# 08_-_CPU_TF_CARD_USB_OTG.net
KiCad netlist of a schematic drawn in Altium Designer
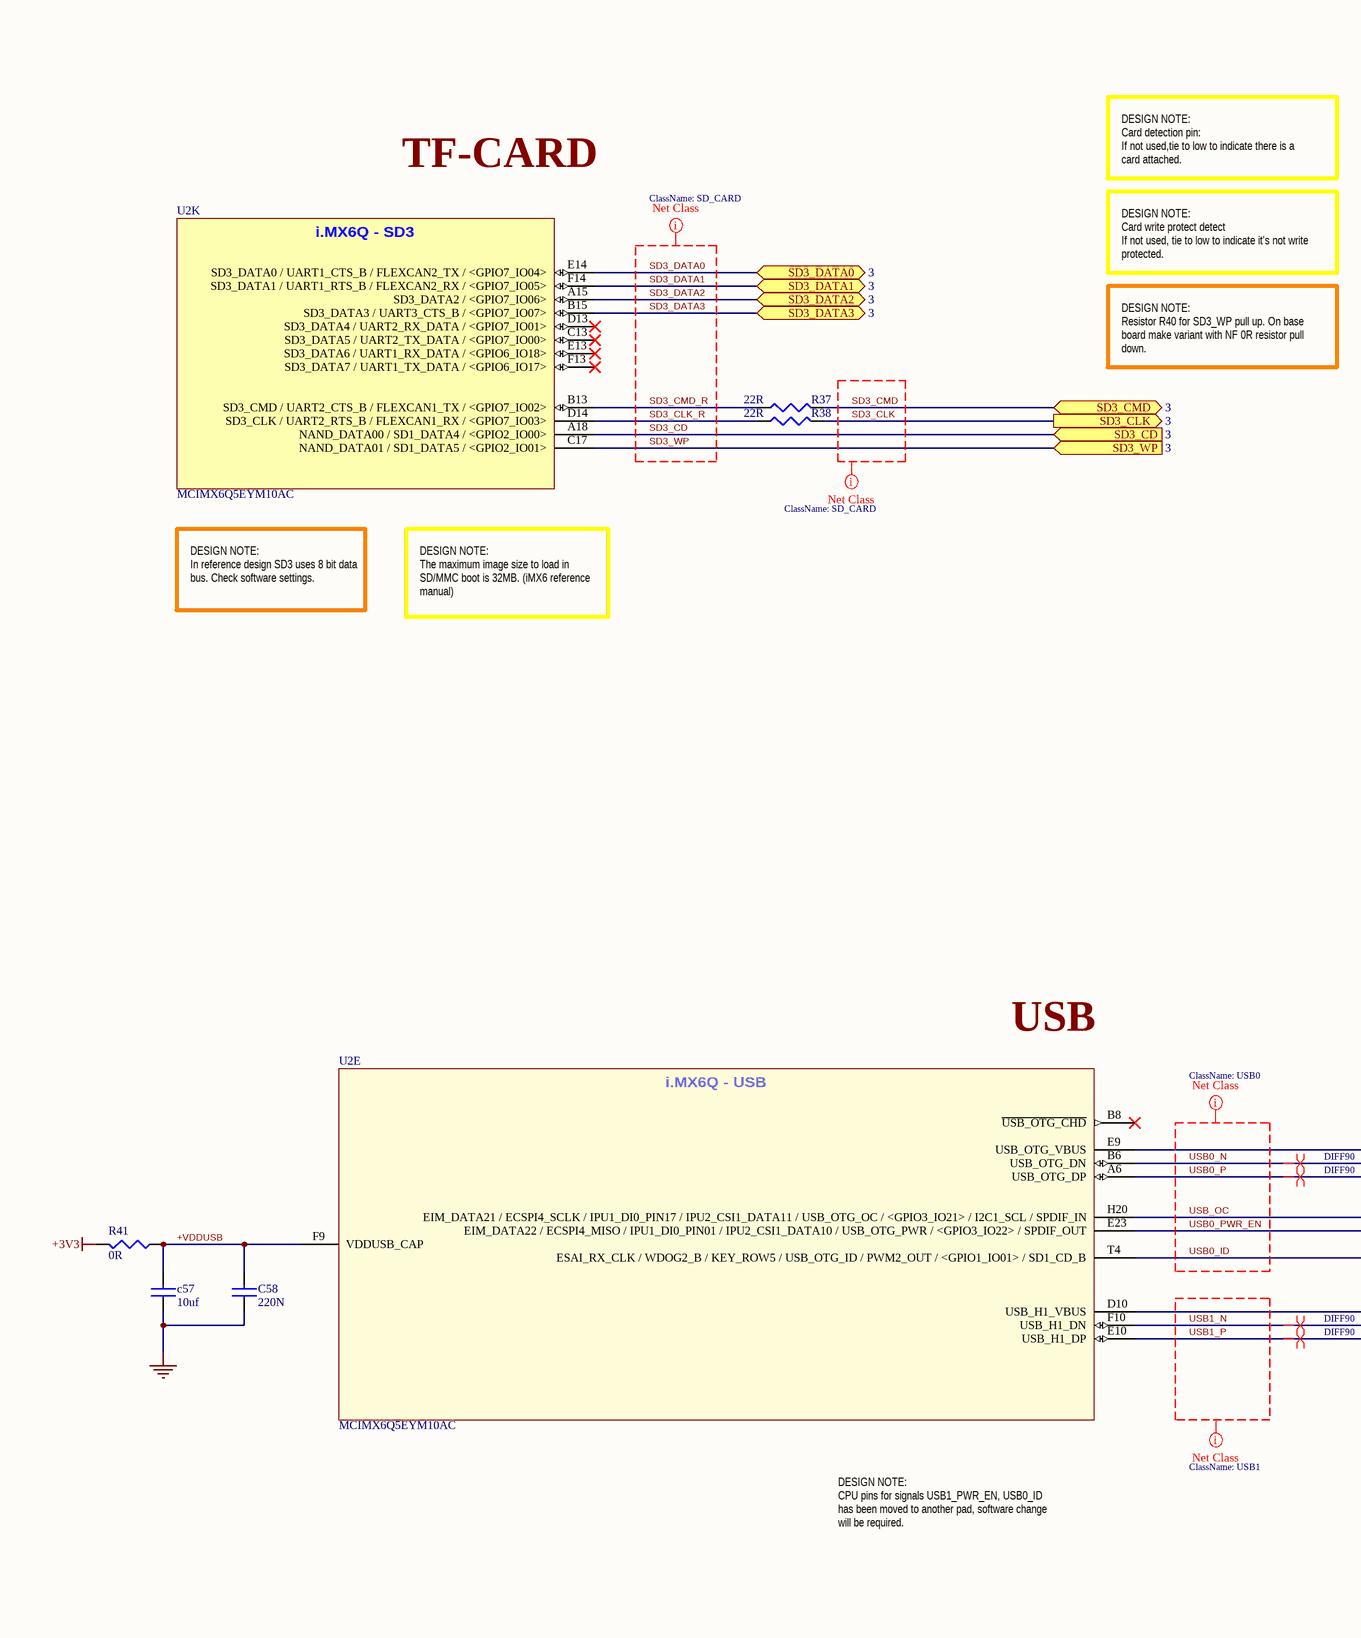
[diagram p0: [08] - CPU TF_CARD,USB OTG.SchDoc, left]
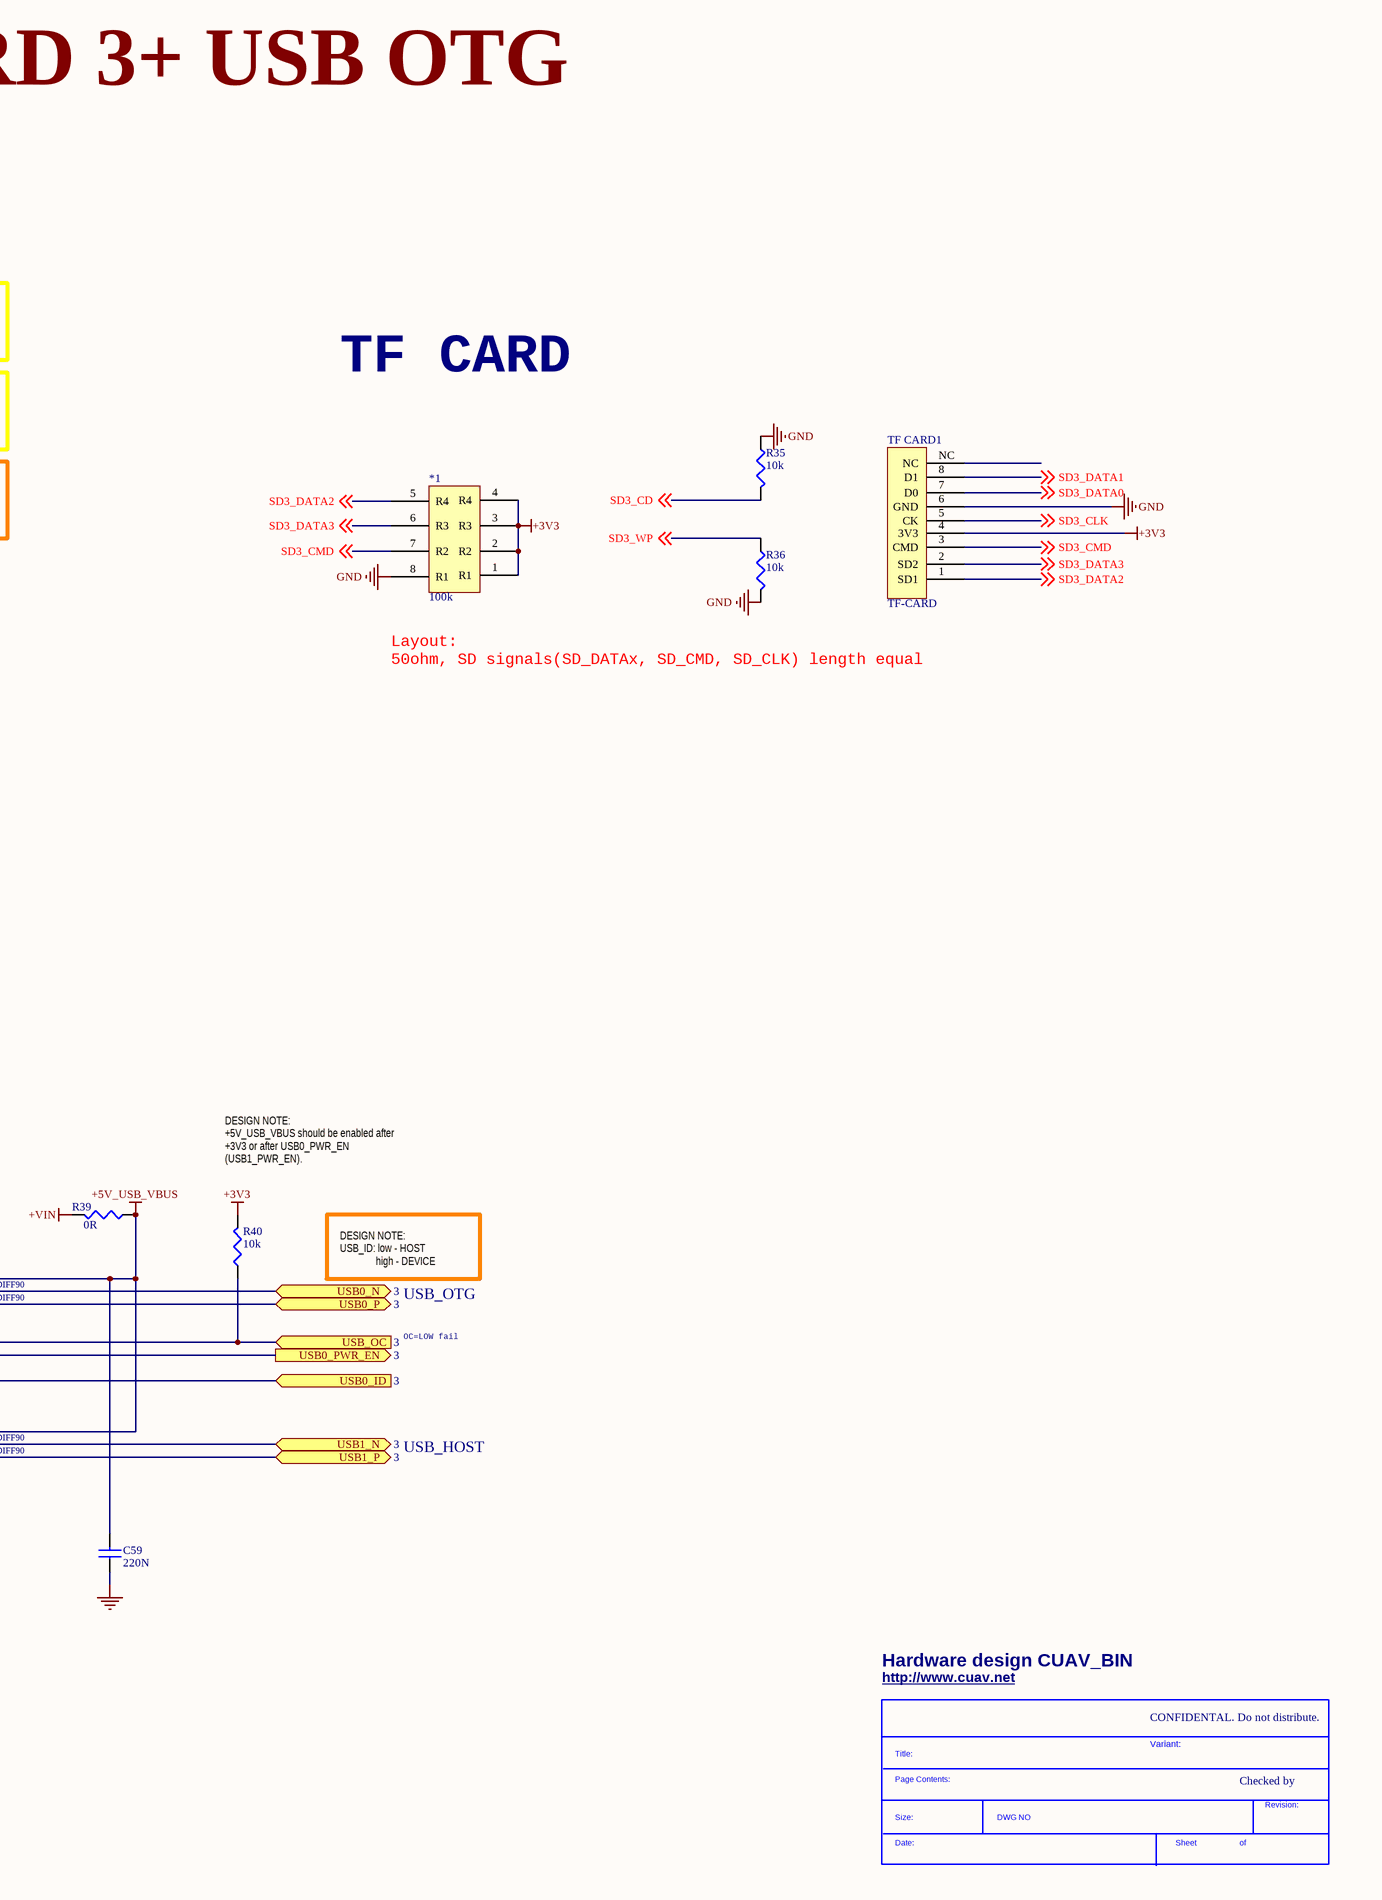
[diagram p1: [08] - CPU TF_CARD,USB OTG.SchDoc, right]

(export (version "E")
  (design (tool "Eeschema 10.0.6"))
  (components
    (comp (ref "*") (value "SDTitleBlock") (libsource (lib "*") (part "SDTitleBlock")))
    (comp (ref "*1") (value "100k") (footprint "0402_4R") (libsource (lib "hack") (part "0402_4R")))
    (comp (ref "c57")
      (value "10uf")
      (footprint "0402cap")
      (description "CAP CER .10UF 50V X5R 10% 0402")
      (fields
        (field (name "MANUFACTURER") "TDK Corporation")
        (field (name "MANUFACTURER PART NUMBER") "C1005X5R1H104K")
      )
      (libsource (lib "Integrated_Library_RF_FEB_2012") (part "C1005X5R1H104K"))
    )
    (comp (ref "C58")
      (value "220N")
      (footprint "0402cap")
      (description "CAP CER .10UF 50V X5R 10% 0402")
      (fields
        (field (name "MANUFACTURER") "TDK Corporation")
        (field (name "MANUFACTURER PART NUMBER") "C1005X5R1H104K")
      )
      (libsource (lib "Integrated_Library_RF_FEB_2012") (part "C1005X5R1H104K"))
    )
    (comp (ref "C59")
      (value "220N")
      (footprint "0402cap")
      (description "CAP CER .10UF 50V X5R 10% 0402")
      (fields
        (field (name "MANUFACTURER") "TDK Corporation")
        (field (name "MANUFACTURER PART NUMBER") "C1005X5R1H104K")
      )
      (libsource (lib "Integrated_Library_RF_FEB_2012") (part "C1005X5R1H104K"))
    )
    (comp (ref "R35")
      (value "10k")
      (footprint "R0402")
      (description "RES 10.0K OHM 1/16W 1% 0402 SMD")
      (fields
        (field (name "MANUFACTURER") "Yageo")
        (field (name "MANUFACTURER PART NUMBER") "RC0402FR-0710KL")
      )
      (libsource (lib "Integrated_Library_RF_FEB_2012") (part "RC0402FR-0710KL"))
    )
    (comp (ref "R36")
      (value "10k")
      (footprint "R0402")
      (description "RES 10.0K OHM 1/16W 1% 0402 SMD")
      (fields
        (field (name "MANUFACTURER") "Yageo")
        (field (name "MANUFACTURER PART NUMBER") "RC0402FR-0710KL")
      )
      (libsource (lib "Integrated_Library_RF_FEB_2012") (part "RC0402FR-0710KL"))
    )
    (comp (ref "R37")
      (value "22R")
      (footprint "R0402")
      (description "RES 22.0 OHM 1/16W 1% 0402 SMD")
      (fields
        (field (name "MANUFACTURER") "Yageo")
        (field (name "MANUFACTURER PART NUMBER") "RC0402FR-0722RL")
      )
      (libsource (lib "Integrated_Library_RF_FEB_2012") (part "RC0402FR-0722RL"))
    )
    (comp (ref "R38")
      (value "22R")
      (footprint "R0402")
      (description "RES 22.0 OHM 1/16W 1% 0402 SMD")
      (fields
        (field (name "MANUFACTURER") "Yageo")
        (field (name "MANUFACTURER PART NUMBER") "RC0402FR-0722RL")
      )
      (libsource (lib "Integrated_Library_RF_FEB_2012") (part "RC0402FR-0722RL"))
    )
    (comp (ref "R39")
      (value "0R")
      (footprint "R0402")
      (description "RES 39.0K OHM 1/16W 1% 0402 SMD")
      (fields
        (field (name "MANUFACTURER") "Yageo")
        (field (name "MANUFACTURER PART NUMBER") "RC0402FR-0739KL")
      )
      (libsource (lib "Integrated_Library_RF_FEB_2012") (part "RC0402FR-0739KL"))
    )
    (comp (ref "R40")
      (value "10k")
      (footprint "R0402")
      (description "RES 10.0K OHM 1/16W 1% 0402 SMD")
      (fields
        (field (name "MANUFACTURER") "Yageo")
        (field (name "MANUFACTURER PART NUMBER") "RC0402FR-0710KL")
      )
      (libsource (lib "Integrated_Library_RF_FEB_2012") (part "RC0402FR-0710KL"))
    )
    (comp (ref "R41")
      (value "0R")
      (footprint "R0402")
      (description "RES 39.0K OHM 1/16W 1% 0402 SMD")
      (fields
        (field (name "MANUFACTURER") "Yageo")
        (field (name "MANUFACTURER PART NUMBER") "RC0402FR-0739KL")
      )
      (libsource (lib "Integrated_Library_RF_FEB_2012") (part "RC0402FR-0739KL"))
    )
    (comp (ref "TF CARD1")
      (value "TF-CARD")
      (footprint "47352-1001")
      (libsource (lib "hack") (part "47352-1001"))
    )
    (comp (ref "U2")
      (value "MCIMX6Q5EYM10AC")
      (footprint "PBGA624")
      (description "IC MCU 32BIT ARM QUAD 624FCBGA")
      (fields
        (field (name "MANUFACTURER") "Freescale Semiconductor")
        (field (name ".CREATOR") "MM")
        (field (name ".CHECKED PCB") "MM, checked by RF")
        (field (name ".CHECKED SCH") "MM")
      )
      (libsource (lib "") (part "MCIMX6Q5EYM10AC_1"))
    )
  )
  (nets
    (net (code "1") (name "+3V3") (class "Default")
      (node (ref "*1") (pin "1") (pinfunction "R1_1") (pintype "passive"))
      (node (ref "*1") (pin "2") (pinfunction "R2_2") (pintype "passive"))
      (node (ref "*1") (pin "3") (pinfunction "R3_3") (pintype "passive"))
      (node (ref "*1") (pin "4") (pinfunction "R4_4") (pintype "passive"))
      (node (ref "R40") (pin "2") (pinfunction "2_2") (pintype "passive"))
      (node (ref "R41") (pin "2") (pinfunction "2_2") (pintype "passive"))
      (node (ref "TF CARD1") (pin "4") (pinfunction "3V3_4") (pintype "passive"))
    )
    (net (code "2") (name "+5V_USB_VBUS") (class "Default")
      (node (ref "C59") (pin "2") (pinfunction "2_2") (pintype "passive"))
      (node (ref "R39") (pin "1") (pinfunction "1_1") (pintype "passive"))
      (node (ref "U2") (pin "D10") (pinfunction "USB_H1_VBUS_D10") (pintype "power_in"))
      (node (ref "U2") (pin "E9") (pinfunction "USB_OTG_VBUS_E9") (pintype "power_in"))
    )
    (net (code "3") (name "+VIN") (class "Default")
      (node (ref "R39") (pin "2") (pinfunction "2_2") (pintype "passive"))
    )
    (net (code "4") (name "/+VDDUSB") (class "Default")
      (node (ref "C58") (pin "2") (pinfunction "2_2") (pintype "passive"))
      (node (ref "R41") (pin "1") (pinfunction "1_1") (pintype "passive"))
      (node (ref "U2") (pin "F9") (pinfunction "VDDUSB_CAP_F9") (pintype "power_in"))
      (node (ref "c57") (pin "2") (pinfunction "2_2") (pintype "passive"))
    )
    (net (code "5") (name "/SD3_CLK_R") (class "Default")
      (node (ref "R38") (pin "1") (pinfunction "1_1") (pintype "passive"))
      (node (ref "U2") (pin "D14") (pinfunction "SD3_CLK_/_UART2_RTS_B_/_FLEXCAN1_RX_/_<GPIO7_IO03>_D14") (pintype "passive"))
    )
    (net (code "6") (name "/SD3_CMD_R") (class "Default")
      (node (ref "R37") (pin "1") (pinfunction "1_1") (pintype "passive"))
      (node (ref "U2") (pin "B13") (pinfunction "SD3_CMD_/_UART2_CTS_B_/_FLEXCAN1_TX_/_<GPIO7_IO02>_B13") (pintype "bidirectional"))
    )
    (net (code "7") (name "/USB0_ID") (class "Default")
      (node (ref "U2") (pin "T4") (pinfunction "ESAI_RX_CLK_/_WDOG2_B_/_KEY_ROW5_/_USB_OTG_ID_/_PWM2_OUT_/_<GPIO1_IO01>_/_SD1_CD_B_T4") (pintype "passive"))
    )
    (net (code "8") (name "/USB0_N") (class "Default")
      (node (ref "U2") (pin "B6") (pinfunction "USB_OTG_DN_B6") (pintype "bidirectional"))
    )
    (net (code "9") (name "/USB0_P") (class "Default")
      (node (ref "U2") (pin "A6") (pinfunction "USB_OTG_DP_A6") (pintype "bidirectional"))
    )
    (net (code "10") (name "/USB0_PWR_EN") (class "Default")
      (node (ref "U2") (pin "E23") (pinfunction "EIM_DATA22_/_ECSPI4_MISO_/_IPU1_DI0_PIN01_/_IPU2_CSI1_DATA10_/_USB_OTG_PWR_/_<GPIO3_IO22>_/_SPDIF_OUT_E23") (pintype "passive"))
    )
    (net (code "11") (name "/USB1_N") (class "Default")
      (node (ref "U2") (pin "F10") (pinfunction "USB_H1_DN_F10") (pintype "bidirectional"))
    )
    (net (code "12") (name "/USB1_P") (class "Default")
      (node (ref "U2") (pin "E10") (pinfunction "USB_H1_DP_E10") (pintype "bidirectional"))
    )
    (net (code "13") (name "/USB_OC") (class "Default")
      (node (ref "R40") (pin "1") (pinfunction "1_1") (pintype "passive"))
      (node (ref "U2") (pin "H20") (pinfunction "EIM_DATA21_/_ECSPI4_SCLK_/_IPU1_DI0_PIN17_/_IPU2_CSI1_DATA11_/_USB_OTG_OC_/_<GPIO3_IO21>_/_I2C1_SCL_/_SPDIF_IN_H20") (pintype "passive"))
    )
    (net (code "14") (name "GND") (class "Default")
      (node (ref "*1") (pin "8") (pinfunction "R1_8") (pintype "passive"))
      (node (ref "C58") (pin "1") (pinfunction "1_1") (pintype "passive"))
      (node (ref "C59") (pin "1") (pinfunction "1_1") (pintype "passive"))
      (node (ref "R35") (pin "1") (pinfunction "1_1") (pintype "passive"))
      (node (ref "R36") (pin "2") (pinfunction "2_2") (pintype "passive"))
      (node (ref "TF CARD1") (pin "6") (pinfunction "GND_6") (pintype "passive"))
      (node (ref "c57") (pin "1") (pinfunction "1_1") (pintype "passive"))
    )
    (net (code "15") (name "SD3_CD") (class "Default")
      (node (ref "R35") (pin "2") (pinfunction "2_2") (pintype "passive"))
      (node (ref "U2") (pin "A18") (pinfunction "NAND_DATA00_/_SD1_DATA4_/_<GPIO2_IO00>_A18") (pintype "passive"))
    )
    (net (code "16") (name "SD3_CLK") (class "Default")
      (node (ref "R38") (pin "2") (pinfunction "2_2") (pintype "passive"))
      (node (ref "TF CARD1") (pin "5") (pinfunction "CK_5") (pintype "passive"))
    )
    (net (code "17") (name "SD3_CMD") (class "Default")
      (node (ref "*1") (pin "7") (pinfunction "R2_7") (pintype "passive"))
      (node (ref "R37") (pin "2") (pinfunction "2_2") (pintype "passive"))
      (node (ref "TF CARD1") (pin "3") (pinfunction "CMD_3") (pintype "passive"))
    )
    (net (code "18") (name "SD3_DATA0") (class "Default")
      (node (ref "TF CARD1") (pin "7") (pinfunction "D0_7") (pintype "passive"))
      (node (ref "U2") (pin "E14") (pinfunction "SD3_DATA0_/_UART1_CTS_B_/_FLEXCAN2_TX_/_<GPIO7_IO04>_E14") (pintype "bidirectional"))
    )
    (net (code "19") (name "SD3_DATA1") (class "Default")
      (node (ref "TF CARD1") (pin "8") (pinfunction "D1_8") (pintype "passive"))
      (node (ref "U2") (pin "F14") (pinfunction "SD3_DATA1_/_UART1_RTS_B_/_FLEXCAN2_RX_/_<GPIO7_IO05>_F14") (pintype "bidirectional"))
    )
    (net (code "20") (name "SD3_DATA2") (class "Default")
      (node (ref "*1") (pin "5") (pinfunction "R4_5") (pintype "passive"))
      (node (ref "TF CARD1") (pin "1") (pinfunction "SD1_1") (pintype "passive"))
      (node (ref "U2") (pin "A15") (pinfunction "SD3_DATA2_/_<GPIO7_IO06>_A15") (pintype "bidirectional"))
    )
    (net (code "21") (name "SD3_DATA3") (class "Default")
      (node (ref "*1") (pin "6") (pinfunction "R3_6") (pintype "passive"))
      (node (ref "TF CARD1") (pin "2") (pinfunction "SD2_2") (pintype "passive"))
      (node (ref "U2") (pin "B15") (pinfunction "SD3_DATA3_/_UART3_CTS_B_/_<GPIO7_IO07>_B15") (pintype "bidirectional"))
    )
    (net (code "22") (name "SD3_WP") (class "Default")
      (node (ref "R36") (pin "1") (pinfunction "1_1") (pintype "passive"))
      (node (ref "U2") (pin "C17") (pinfunction "NAND_DATA01_/_SD1_DATA5_/_<GPIO2_IO01>_C17") (pintype "passive"))
    )
    (net (code "23") (name "unconnected-(TF CARD1-PadNC)") (class "Default")
      (node (ref "TF CARD1") (pin "NC") (pinfunction "NC_NC") (pintype "passive"))
    )
    (net (code "24") (name "unconnected-(U2E-~{USB_OTG_CHD}-PadB8)") (class "Default")
      (node (ref "U2") (pin "B8") (pinfunction "~{USB_OTG_CHD}_B8") (pintype "output+no_connect"))
    )
    (net (code "25") (name "unconnected-(U2K-SD3_DATA4_{slash}_UART2_RX_DATA_{slash}_<GPIO7_IO01>-PadD13)") (class "Default")
      (node (ref "U2") (pin "D13") (pinfunction "SD3_DATA4_/_UART2_RX_DATA_/_<GPIO7_IO01>_D13") (pintype "bidirectional+no_connect"))
    )
    (net (code "26") (name "unconnected-(U2K-SD3_DATA5_{slash}_UART2_TX_DATA_{slash}_<GPIO7_IO00>-PadC13)") (class "Default")
      (node (ref "U2") (pin "C13") (pinfunction "SD3_DATA5_/_UART2_TX_DATA_/_<GPIO7_IO00>_C13") (pintype "bidirectional+no_connect"))
    )
    (net (code "27") (name "unconnected-(U2K-SD3_DATA6_{slash}_UART1_RX_DATA_{slash}_<GPIO6_IO18>-PadE13)") (class "Default")
      (node (ref "U2") (pin "E13") (pinfunction "SD3_DATA6_/_UART1_RX_DATA_/_<GPIO6_IO18>_E13") (pintype "bidirectional+no_connect"))
    )
    (net (code "28") (name "unconnected-(U2K-SD3_DATA7_{slash}_UART1_TX_DATA_{slash}_<GPIO6_IO17>-PadF13)") (class "Default")
      (node (ref "U2") (pin "F13") (pinfunction "SD3_DATA7_/_UART1_TX_DATA_/_<GPIO6_IO17>_F13") (pintype "bidirectional+no_connect"))
    )
  )
)
